# scoreledboard.net
KiCad netlist of a schematic drawn in EAGLE
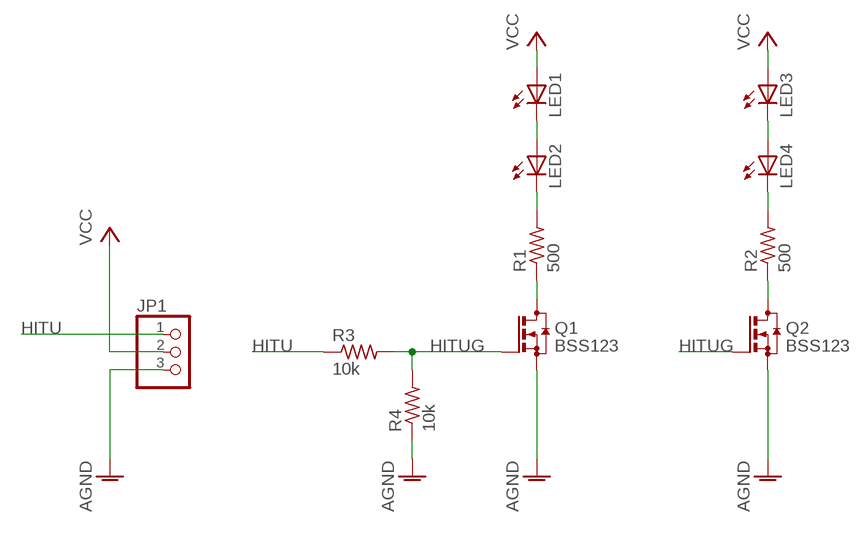
[diagram p0: schematic, sheet 1]

(export (version "E")
  (design (tool "Eeschema 10.0.6"))
  (components
    (comp (ref "JP1")
      (value "PINHD-1X3")
      (footprint "eagle-import:1X03")
      (libsource (lib "eagle-import") (part "PINHD-1X3"))
    )
    (comp (ref "LED1")
      (value "LEDCHIPLED_1206")
      (footprint "eagle-import:CHIPLED_1206")
      (libsource (lib "eagle-import") (part "LEDCHIPLED_1206"))
    )
    (comp (ref "LED2")
      (value "LEDCHIPLED_1206")
      (footprint "eagle-import:CHIPLED_1206")
      (libsource (lib "eagle-import") (part "LEDCHIPLED_1206"))
    )
    (comp (ref "LED3")
      (value "LEDCHIPLED_1206")
      (footprint "eagle-import:CHIPLED_1206")
      (libsource (lib "eagle-import") (part "LEDCHIPLED_1206"))
    )
    (comp (ref "LED4")
      (value "LEDCHIPLED_1206")
      (footprint "eagle-import:CHIPLED_1206")
      (libsource (lib "eagle-import") (part "LEDCHIPLED_1206"))
    )
    (comp (ref "Q1")
      (value "BSS123")
      (footprint "eagle-import:SOT23")
      (libsource (lib "eagle-import") (part "BSS123"))
    )
    (comp (ref "Q2")
      (value "BSS123")
      (footprint "eagle-import:SOT23")
      (libsource (lib "eagle-import") (part "BSS123"))
    )
    (comp (ref "R1")
      (value "500")
      (footprint "eagle-import:R1206")
      (libsource (lib "eagle-import") (part "R-US_R1206"))
    )
    (comp (ref "R2")
      (value "500")
      (footprint "eagle-import:R1206")
      (libsource (lib "eagle-import") (part "R-US_R1206"))
    )
    (comp (ref "R3")
      (value "10k")
      (footprint "eagle-import:R1206")
      (libsource (lib "eagle-import") (part "R-US_R1206"))
    )
    (comp (ref "R4")
      (value "10k")
      (footprint "eagle-import:R1206")
      (libsource (lib "eagle-import") (part "R-US_R1206"))
    )
  )
  (nets
    (net (code "1") (name "/HITU") (class "Default")
      (node (ref "JP1") (pin "1") (pinfunction "1_1") (pintype "passive"))
      (node (ref "R3") (pin "1") (pinfunction "1_1") (pintype "passive"))
    )
    (net (code "2") (name "/HITUG") (class "Default")
      (node (ref "Q1") (pin "1") (pinfunction "G_1") (pintype "passive"))
      (node (ref "Q2") (pin "1") (pinfunction "G_1") (pintype "passive"))
      (node (ref "R3") (pin "2") (pinfunction "2_2") (pintype "passive"))
      (node (ref "R4") (pin "2") (pinfunction "2_2") (pintype "passive"))
    )
    (net (code "3") (name "AGND") (class "Default")
      (node (ref "JP1") (pin "3") (pinfunction "3_3") (pintype "passive"))
      (node (ref "Q1") (pin "2") (pinfunction "S_2") (pintype "passive"))
      (node (ref "Q2") (pin "2") (pinfunction "S_2") (pintype "passive"))
      (node (ref "R4") (pin "1") (pinfunction "1_1") (pintype "passive"))
    )
    (net (code "4") (name "Net-(LED1-PadC)") (class "Default")
      (node (ref "LED1") (pin "C") (pinfunction "C_C") (pintype "passive"))
      (node (ref "LED2") (pin "A") (pinfunction "A_A") (pintype "passive"))
    )
    (net (code "5") (name "Net-(LED2-PadC)") (class "Default")
      (node (ref "LED2") (pin "C") (pinfunction "C_C") (pintype "passive"))
      (node (ref "R1") (pin "2") (pinfunction "2_2") (pintype "passive"))
    )
    (net (code "6") (name "Net-(LED3-PadC)") (class "Default")
      (node (ref "LED3") (pin "C") (pinfunction "C_C") (pintype "passive"))
      (node (ref "LED4") (pin "A") (pinfunction "A_A") (pintype "passive"))
    )
    (net (code "7") (name "Net-(LED4-PadC)") (class "Default")
      (node (ref "LED4") (pin "C") (pinfunction "C_C") (pintype "passive"))
      (node (ref "R2") (pin "2") (pinfunction "2_2") (pintype "passive"))
    )
    (net (code "8") (name "Net-(Q1-D)") (class "Default")
      (node (ref "Q1") (pin "3") (pinfunction "D_3") (pintype "passive"))
      (node (ref "R1") (pin "1") (pinfunction "1_1") (pintype "passive"))
    )
    (net (code "9") (name "Net-(Q2-D)") (class "Default")
      (node (ref "Q2") (pin "3") (pinfunction "D_3") (pintype "passive"))
      (node (ref "R2") (pin "1") (pinfunction "1_1") (pintype "passive"))
    )
    (net (code "10") (name "VCC") (class "Default")
      (node (ref "JP1") (pin "2") (pinfunction "2_2") (pintype "passive"))
      (node (ref "LED1") (pin "A") (pinfunction "A_A") (pintype "passive"))
      (node (ref "LED3") (pin "A") (pinfunction "A_A") (pintype "passive"))
    )
  )
)
